# ENC28j60_Ethernet.net
KiCad netlist of a schematic drawn in Altium Designer
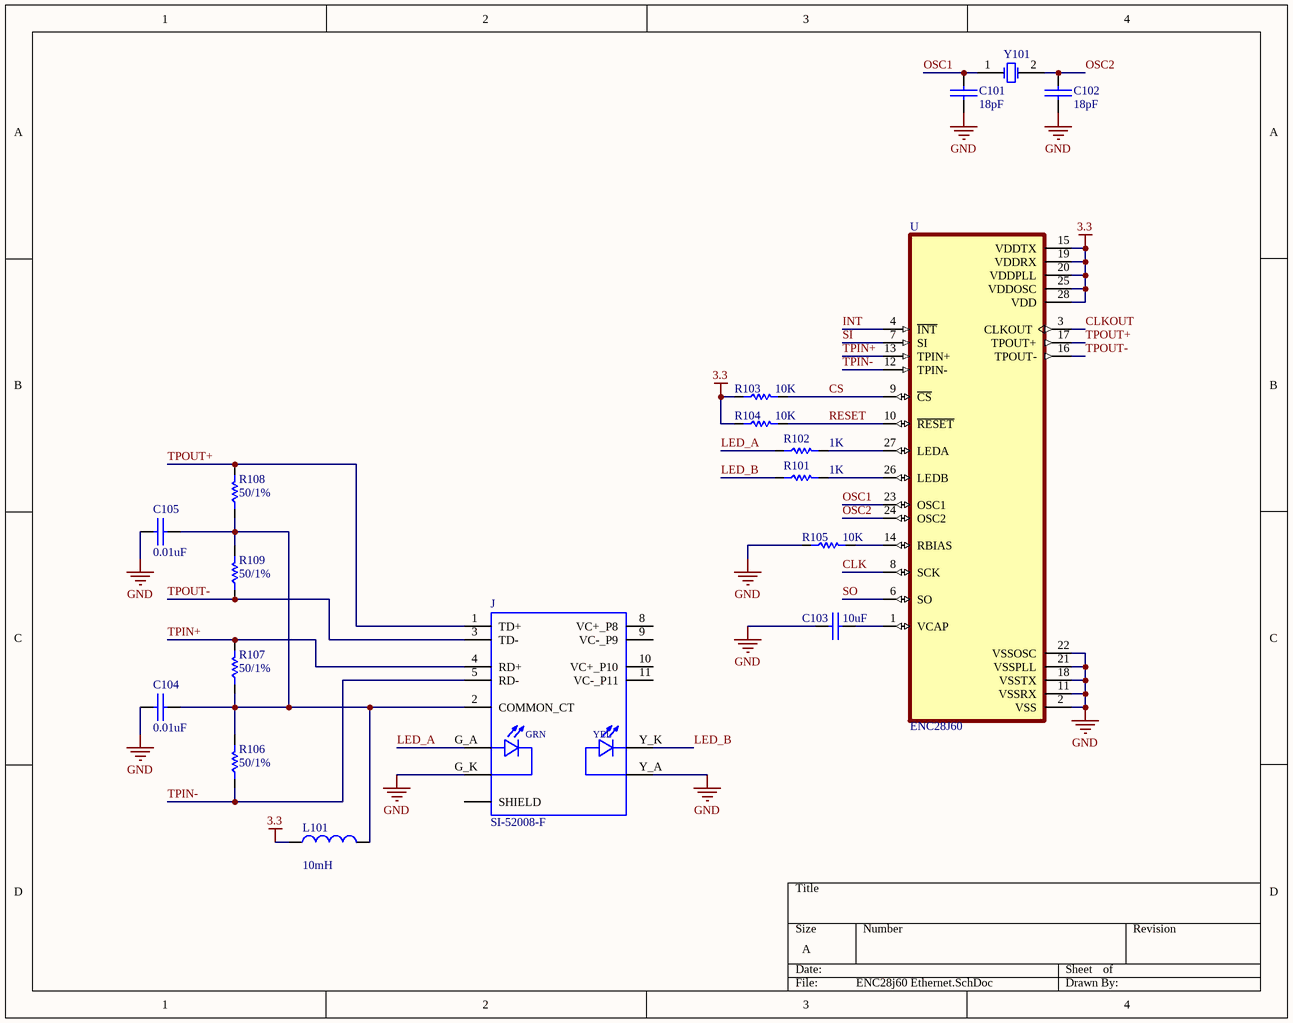
[diagram p0: ENC28j60 Ethernet.SchDoc]

(export (version "E")
  (design (tool "Eeschema 10.0.6"))
  (components
    (comp (ref "C101")
      (value "18pF")
      (footprint "SMD_CAP_0805")
      (description "Bipolar Capacitor")
      (fields (field (name "VOLTAGE") "100V") (field (name "DESIGNER") "Saeid Jorablo"))
      (libsource (lib "DDEms") (part "Cap-Bipolar"))
    )
    (comp (ref "C102")
      (value "18pF")
      (footprint "SMD_CAP_0805")
      (description "Bipolar Capacitor")
      (fields (field (name "VOLTAGE") "100V") (field (name "DESIGNER") "Saeid Jorablo"))
      (libsource (lib "DDEms") (part "Cap-Bipolar"))
    )
    (comp (ref "C103")
      (value "10uF")
      (footprint "SMD_CAP_0805")
      (description "Bipolar Capacitor")
      (fields (field (name "VOLTAGE") "100V") (field (name "DESIGNER") "Saeid Jorablo"))
      (libsource (lib "DDEms") (part "Cap-Bipolar"))
    )
    (comp (ref "C104")
      (value "0.01uF")
      (footprint "SMD_CAP_0805")
      (description "Bipolar Capacitor")
      (fields (field (name "VOLTAGE") "100V") (field (name "DESIGNER") "Saeid Jorablo"))
      (libsource (lib "DDEms") (part "Cap-Bipolar"))
    )
    (comp (ref "C105")
      (value "0.01uF")
      (footprint "SMD_CAP_0805")
      (description "Bipolar Capacitor")
      (fields (field (name "VOLTAGE") "100V") (field (name "DESIGNER") "Saeid Jorablo"))
      (libsource (lib "DDEms") (part "Cap-Bipolar"))
    )
    (comp (ref "J")
      (value "SI-52008-F")
      (footprint "BEL_SI-52008-F")
      (description "1 Port RJ45 Magjack Connector Through Hole 10/100 Base-T, AutoMDIX, Power over Ethernet _PoE_")
      (fields (field (name "MF") "Stewart Connector"))
      (libsource (lib "SI-52008-F") (part "SI-52008-F"))
    )
    (comp (ref "L101")
      (value "10mH")
      (footprint "INDC1608L")
      (description "Inductor")
      (fields (field (name "PUBLISHER") "Altium Limited"))
      (libsource (lib "DDEms") (part "Inductor"))
    )
    (comp (ref "R101")
      (value "1K")
      (footprint "RES 0805 (2012X06L)")
      (description "Resistor")
      (fields (field (name "TOLERANCE") "5%") (field (name "POWER") "1/8 W"))
      (libsource (lib "DDEms") (part "Resistor"))
    )
    (comp (ref "R102")
      (value "1K")
      (footprint "RES 0805 (2012X06L)")
      (description "Resistor")
      (fields (field (name "TOLERANCE") "5%") (field (name "POWER") "1/8 W"))
      (libsource (lib "DDEms") (part "Resistor"))
    )
    (comp (ref "R103")
      (value "10K")
      (footprint "RES 0805 (2012X06L)")
      (description "Resistor")
      (fields (field (name "TOLERANCE") "5%") (field (name "POWER") "1/8 W"))
      (libsource (lib "DDEms") (part "Resistor"))
    )
    (comp (ref "R104")
      (value "10K")
      (footprint "RES 0805 (2012X06L)")
      (description "Resistor")
      (fields (field (name "TOLERANCE") "5%") (field (name "POWER") "1/8 W"))
      (libsource (lib "DDEms") (part "Resistor"))
    )
    (comp (ref "R105")
      (value "10K")
      (footprint "RES 0805 (2012X06L)")
      (description "Resistor")
      (fields (field (name "TOLERANCE") "5%") (field (name "POWER") "1/8 W"))
      (libsource (lib "DDEms") (part "Resistor"))
    )
    (comp (ref "R106")
      (value "50/1%")
      (footprint "RES 0805 (2012X06L)")
      (description "Resistor")
      (fields (field (name "TOLERANCE") "5%") (field (name "POWER") "1/8 W"))
      (libsource (lib "DDEms") (part "Resistor"))
    )
    (comp (ref "R107")
      (value "50/1%")
      (footprint "RES 0805 (2012X06L)")
      (description "Resistor")
      (fields (field (name "TOLERANCE") "5%") (field (name "POWER") "1/8 W"))
      (libsource (lib "DDEms") (part "Resistor"))
    )
    (comp (ref "R108")
      (value "50/1%")
      (footprint "RES 0805 (2012X06L)")
      (description "Resistor")
      (fields (field (name "TOLERANCE") "5%") (field (name "POWER") "1/8 W"))
      (libsource (lib "DDEms") (part "Resistor"))
    )
    (comp (ref "R109")
      (value "50/1%")
      (footprint "RES 0805 (2012X06L)")
      (description "Resistor")
      (fields (field (name "TOLERANCE") "5%") (field (name "POWER") "1/8 W"))
      (libsource (lib "DDEms") (part "Resistor"))
    )
    (comp (ref "U")
      (value "ENC28J60")
      (footprint "SOIC127P1030X265-28N")
      (description "Ethernet Controller 10 Base-T PHY SPI Interface 28-SSOP")
      (fields (field (name "MF") "Microchip"))
      (libsource (lib "ENC28J60") (part "ENC28J60"))
    )
    (comp (ref "Y101")
      (value "11.0592 MHz")
      (footprint "Crystal SMD")
      (description "XTAL Crystal")
      (libsource (lib "DDEms") (part "XTAL"))
    )
  )
  (nets
    (net (code "1") (name "/CLK") (class "Default")
      (node (ref "U") (pin "8") (pinfunction "SCK_8") (pintype "bidirectional"))
    )
    (net (code "2") (name "/CLKOUT") (class "Default")
      (node (ref "U") (pin "3") (pinfunction "CLKOUT_3") (pintype "output"))
    )
    (net (code "3") (name "/CS") (class "Default")
      (node (ref "R103") (pin "2") (pinfunction "2_2") (pintype "passive"))
      (node (ref "U") (pin "9") (pinfunction "~{CS}_9") (pintype "bidirectional"))
    )
    (net (code "4") (name "/INT") (class "Default")
      (node (ref "U") (pin "4") (pinfunction "~{INT}_4") (pintype "input"))
    )
    (net (code "5") (name "/LED_A") (class "Default")
      (node (ref "J") (pin "G_A") (pinfunction "G_A_G_A") (pintype "passive"))
      (node (ref "R102") (pin "1") (pinfunction "1_1") (pintype "passive"))
    )
    (net (code "6") (name "/LED_B") (class "Default")
      (node (ref "J") (pin "Y_K") (pinfunction "Y_K_Y_K") (pintype "passive"))
      (node (ref "R101") (pin "1") (pinfunction "1_1") (pintype "passive"))
    )
    (net (code "7") (name "/OSC1") (class "Default")
      (node (ref "C101") (pin "1") (pinfunction "+_1") (pintype "passive"))
      (node (ref "U") (pin "23") (pinfunction "OSC1_23") (pintype "bidirectional"))
      (node (ref "Y101") (pin "1") (pinfunction "OSC1_1") (pintype "passive"))
    )
    (net (code "8") (name "/OSC2") (class "Default")
      (node (ref "C102") (pin "1") (pinfunction "+_1") (pintype "passive"))
      (node (ref "U") (pin "24") (pinfunction "OSC2_24") (pintype "bidirectional"))
      (node (ref "Y101") (pin "2") (pinfunction "OSC2_2") (pintype "passive"))
    )
    (net (code "9") (name "/RESET") (class "Default")
      (node (ref "R104") (pin "2") (pinfunction "2_2") (pintype "passive"))
      (node (ref "U") (pin "10") (pinfunction "~{RESET}_10") (pintype "bidirectional"))
    )
    (net (code "10") (name "/SI") (class "Default")
      (node (ref "U") (pin "7") (pinfunction "SI_7") (pintype "input"))
    )
    (net (code "11") (name "/SO") (class "Default")
      (node (ref "U") (pin "6") (pinfunction "SO_6") (pintype "bidirectional"))
    )
    (net (code "12") (name "/TPIN+") (class "Default")
      (node (ref "J") (pin "4") (pinfunction "RD+_4") (pintype "passive"))
      (node (ref "R107") (pin "2") (pinfunction "2_2") (pintype "passive"))
      (node (ref "U") (pin "13") (pinfunction "TPIN+_13") (pintype "input"))
    )
    (net (code "13") (name "/TPIN-") (class "Default")
      (node (ref "J") (pin "5") (pinfunction "RD-_5") (pintype "passive"))
      (node (ref "R106") (pin "1") (pinfunction "1_1") (pintype "passive"))
      (node (ref "U") (pin "12") (pinfunction "TPIN-_12") (pintype "input"))
    )
    (net (code "14") (name "/TPOUT+") (class "Default")
      (node (ref "J") (pin "1") (pinfunction "TD+_1") (pintype "passive"))
      (node (ref "R108") (pin "2") (pinfunction "2_2") (pintype "passive"))
      (node (ref "U") (pin "17") (pinfunction "TPOUT+_17") (pintype "output"))
    )
    (net (code "15") (name "/TPOUT-") (class "Default")
      (node (ref "J") (pin "3") (pinfunction "TD-_3") (pintype "passive"))
      (node (ref "R109") (pin "1") (pinfunction "1_1") (pintype "passive"))
      (node (ref "U") (pin "16") (pinfunction "TPOUT-_16") (pintype "output"))
    )
    (net (code "16") (name "3.3") (class "Default")
      (node (ref "L101") (pin "1") (pinfunction "1_1") (pintype "passive"))
      (node (ref "R103") (pin "1") (pinfunction "1_1") (pintype "passive"))
      (node (ref "R104") (pin "1") (pinfunction "1_1") (pintype "passive"))
      (node (ref "U") (pin "15") (pinfunction "VDDTX_15") (pintype "power_in"))
      (node (ref "U") (pin "19") (pinfunction "VDDRX_19") (pintype "power_in"))
      (node (ref "U") (pin "20") (pinfunction "VDDPLL_20") (pintype "power_in"))
      (node (ref "U") (pin "25") (pinfunction "VDDOSC_25") (pintype "power_in"))
      (node (ref "U") (pin "28") (pinfunction "VDD_28") (pintype "power_in"))
    )
    (net (code "17") (name "GND") (class "Default")
      (node (ref "C101") (pin "2") (pinfunction "-_2") (pintype "passive"))
      (node (ref "C102") (pin "2") (pinfunction "-_2") (pintype "passive"))
      (node (ref "C103") (pin "1") (pinfunction "+_1") (pintype "passive"))
      (node (ref "C104") (pin "1") (pinfunction "+_1") (pintype "passive"))
      (node (ref "C105") (pin "1") (pinfunction "+_1") (pintype "passive"))
      (node (ref "J") (pin "G_K") (pinfunction "G_K_G_K") (pintype "passive"))
      (node (ref "J") (pin "Y_A") (pinfunction "Y_A_Y_A") (pintype "passive"))
      (node (ref "R105") (pin "1") (pinfunction "1_1") (pintype "passive"))
      (node (ref "U") (pin "11") (pinfunction "VSSRX_11") (pintype "power_in"))
      (node (ref "U") (pin "18") (pinfunction "VSSTX_18") (pintype "power_in"))
      (node (ref "U") (pin "2") (pinfunction "VSS_2") (pintype "power_in"))
      (node (ref "U") (pin "21") (pinfunction "VSSPLL_21") (pintype "power_in"))
      (node (ref "U") (pin "22") (pinfunction "VSSOSC_22") (pintype "power_in"))
    )
    (net (code "18") (name "Net-(C103--)") (class "Default")
      (node (ref "C103") (pin "2") (pinfunction "-_2") (pintype "passive"))
      (node (ref "U") (pin "1") (pinfunction "VCAP_1") (pintype "bidirectional"))
    )
    (net (code "19") (name "Net-(C104--)") (class "Default")
      (node (ref "C104") (pin "2") (pinfunction "-_2") (pintype "passive"))
      (node (ref "C105") (pin "2") (pinfunction "-_2") (pintype "passive"))
      (node (ref "J") (pin "2") (pinfunction "COMMON_CT_2") (pintype "passive"))
      (node (ref "L101") (pin "2") (pinfunction "2_2") (pintype "passive"))
      (node (ref "R106") (pin "2") (pinfunction "2_2") (pintype "passive"))
      (node (ref "R107") (pin "1") (pinfunction "1_1") (pintype "passive"))
      (node (ref "R108") (pin "1") (pinfunction "1_1") (pintype "passive"))
      (node (ref "R109") (pin "2") (pinfunction "2_2") (pintype "passive"))
    )
    (net (code "20") (name "Net-(J-SHIELD-PadS1)") (class "Default")
      (node (ref "J") (pin "S1") (pinfunction "SHIELD_S1") (pintype "passive"))
      (node (ref "J") (pin "S2") (pinfunction "SHIELD_S2") (pintype "passive"))
    )
    (net (code "21") (name "Net-(U-LEDA)") (class "Default")
      (node (ref "R102") (pin "2") (pinfunction "2_2") (pintype "passive"))
      (node (ref "U") (pin "27") (pinfunction "LEDA_27") (pintype "bidirectional"))
    )
    (net (code "22") (name "Net-(U-LEDB)") (class "Default")
      (node (ref "R101") (pin "2") (pinfunction "2_2") (pintype "passive"))
      (node (ref "U") (pin "26") (pinfunction "LEDB_26") (pintype "bidirectional"))
    )
    (net (code "23") (name "Net-(U-RBIAS)") (class "Default")
      (node (ref "R105") (pin "2") (pinfunction "2_2") (pintype "passive"))
      (node (ref "U") (pin "14") (pinfunction "RBIAS_14") (pintype "bidirectional"))
    )
    (net (code "24") (name "unconnected-(J-VC+_P8-Pad8)") (class "Default")
      (node (ref "J") (pin "8") (pinfunction "VC+_P8_8") (pintype "passive"))
    )
    (net (code "25") (name "unconnected-(J-VC+_P10-Pad10)") (class "Default")
      (node (ref "J") (pin "10") (pinfunction "VC+_P10_10") (pintype "passive"))
    )
    (net (code "26") (name "unconnected-(J-VC-_P9-Pad9)") (class "Default")
      (node (ref "J") (pin "9") (pinfunction "VC-_P9_9") (pintype "passive"))
    )
    (net (code "27") (name "unconnected-(J-VC-_P11-Pad11)") (class "Default")
      (node (ref "J") (pin "11") (pinfunction "VC-_P11_11") (pintype "passive"))
    )
  )
)
